# MMIRRecSys.net
KiCad netlist of a schematic drawn in EAGLE
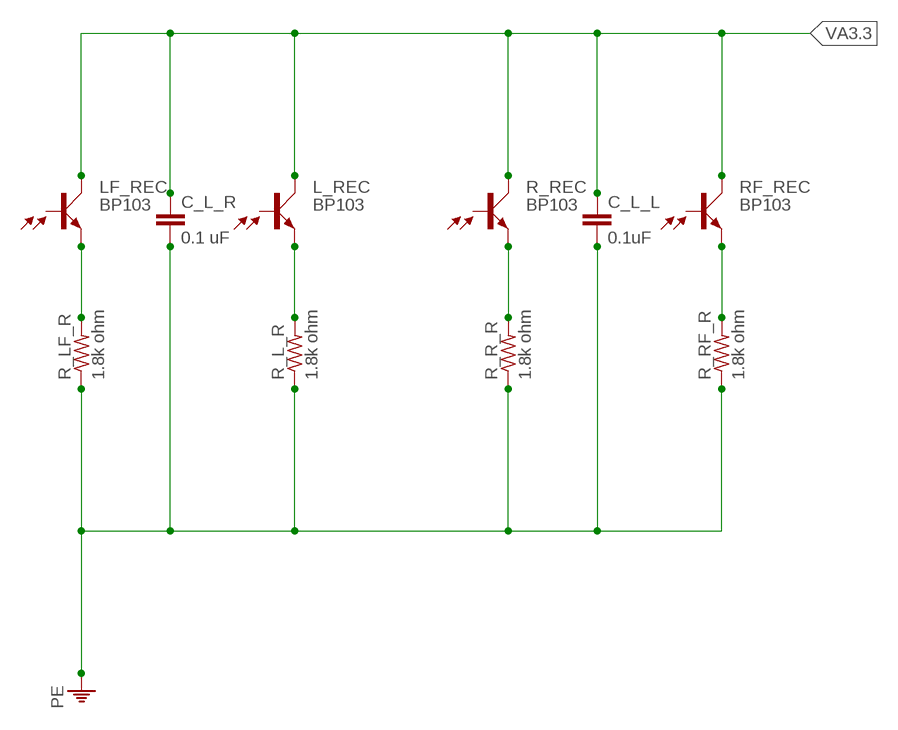
[diagram p0: schematic, sheet 1]

(export (version "E")
  (design (tool "Eeschema 10.0.6"))
  (components
    (comp (ref "C_L_L")
      (value "0.1uF")
      (footprint "eagle-import:C1206")
      (libsource (lib "eagle-import") (part "C-EUC1206"))
    )
    (comp (ref "C_L_R")
      (value "0.1 uF")
      (footprint "eagle-import:C1206")
      (libsource (lib "eagle-import") (part "C-EUC1206"))
    )
    (comp (ref "LF_REC")
      (value "BP103")
      (footprint "eagle-import:BP103")
      (libsource (lib "eagle-import") (part "BP103"))
    )
    (comp (ref "L_REC")
      (value "BP103")
      (footprint "eagle-import:BP103")
      (libsource (lib "eagle-import") (part "BP103"))
    )
    (comp (ref "RF_REC")
      (value "BP103")
      (footprint "eagle-import:BP103")
      (libsource (lib "eagle-import") (part "BP103"))
    )
    (comp (ref "R_LF_R")
      (value "1.8k ohm")
      (footprint "eagle-import:R1206")
      (libsource (lib "eagle-import") (part "R-US_R1206"))
    )
    (comp (ref "R_L_R")
      (value "1.8k ohm")
      (footprint "eagle-import:R1206")
      (libsource (lib "eagle-import") (part "R-US_R1206"))
    )
    (comp (ref "R_REC")
      (value "BP103")
      (footprint "eagle-import:BP103")
      (libsource (lib "eagle-import") (part "BP103"))
    )
    (comp (ref "R_RF_R")
      (value "1.8k ohm")
      (footprint "eagle-import:R1206")
      (libsource (lib "eagle-import") (part "R-US_R1206"))
    )
    (comp (ref "R_R_R")
      (value "1.8k ohm")
      (footprint "eagle-import:R1206")
      (libsource (lib "eagle-import") (part "R-US_R1206"))
    )
  )
  (nets
    (net (code "1") (name "Net-(LF_REC-PadE)") (class "Default")
      (node (ref "LF_REC") (pin "E") (pinfunction "E_E") (pintype "passive"))
      (node (ref "R_LF_R") (pin "2") (pinfunction "2_2") (pintype "passive"))
    )
    (net (code "2") (name "Net-(L_REC-PadE)") (class "Default")
      (node (ref "L_REC") (pin "E") (pinfunction "E_E") (pintype "passive"))
      (node (ref "R_L_R") (pin "2") (pinfunction "2_2") (pintype "passive"))
    )
    (net (code "3") (name "Net-(RF_REC-PadE)") (class "Default")
      (node (ref "RF_REC") (pin "E") (pinfunction "E_E") (pintype "passive"))
      (node (ref "R_RF_R") (pin "2") (pinfunction "2_2") (pintype "passive"))
    )
    (net (code "4") (name "Net-(R_REC-PadE)") (class "Default")
      (node (ref "R_REC") (pin "E") (pinfunction "E_E") (pintype "passive"))
      (node (ref "R_R_R") (pin "2") (pinfunction "2_2") (pintype "passive"))
    )
    (net (code "5") (name "PE") (class "Default")
      (node (ref "C_L_L") (pin "2") (pinfunction "2_2") (pintype "passive"))
      (node (ref "C_L_R") (pin "2") (pinfunction "2_2") (pintype "passive"))
      (node (ref "R_LF_R") (pin "1") (pinfunction "1_1") (pintype "passive"))
      (node (ref "R_L_R") (pin "1") (pinfunction "1_1") (pintype "passive"))
      (node (ref "R_RF_R") (pin "1") (pinfunction "1_1") (pintype "passive"))
      (node (ref "R_R_R") (pin "1") (pinfunction "1_1") (pintype "passive"))
    )
    (net (code "6") (name "VA3.3") (class "Default")
      (node (ref "C_L_L") (pin "1") (pinfunction "1_1") (pintype "passive"))
      (node (ref "C_L_R") (pin "1") (pinfunction "1_1") (pintype "passive"))
      (node (ref "LF_REC") (pin "C") (pinfunction "C_C") (pintype "passive"))
      (node (ref "L_REC") (pin "C") (pinfunction "C_C") (pintype "passive"))
      (node (ref "RF_REC") (pin "C") (pinfunction "C_C") (pintype "passive"))
      (node (ref "R_REC") (pin "C") (pinfunction "C_C") (pintype "passive"))
    )
    (net (code "7") (name "unconnected-(LF_REC-PadB)") (class "Default")
      (node (ref "LF_REC") (pin "B") (pinfunction "B_B") (pintype "passive"))
    )
    (net (code "8") (name "unconnected-(L_REC-PadB)") (class "Default")
      (node (ref "L_REC") (pin "B") (pinfunction "B_B") (pintype "passive"))
    )
    (net (code "9") (name "unconnected-(RF_REC-PadB)") (class "Default")
      (node (ref "RF_REC") (pin "B") (pinfunction "B_B") (pintype "passive"))
    )
    (net (code "10") (name "unconnected-(R_REC-PadB)") (class "Default")
      (node (ref "R_REC") (pin "B") (pinfunction "B_B") (pintype "passive"))
    )
  )
)
